# Power.net
KiCad netlist of a schematic drawn in EAGLE
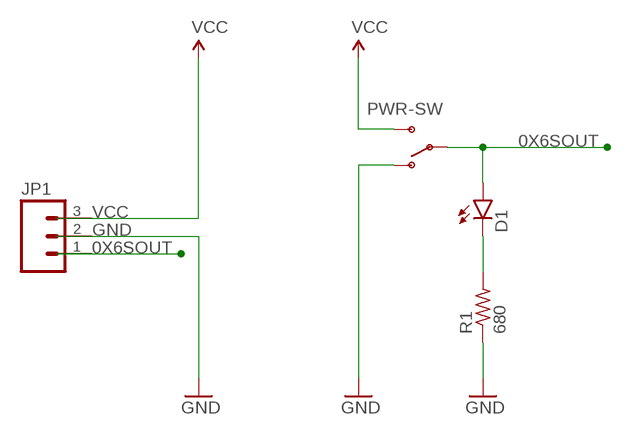
[diagram p0: schematic, sheet 1]

(export (version "E")
  (design (tool "Eeschema 10.0.6"))
  (components
    (comp (ref "D1")
      (value "LED3MM")
      (footprint "eagle-import:LED3MM")
      (libsource (lib "eagle-import") (part "LED3MM"))
    )
    (comp (ref "JP1")
      (value "M03PTH")
      (footprint "eagle-import:1X03")
      (libsource (lib "eagle-import") (part "M03PTH"))
    )
    (comp (ref "PWR-SW")
      (value "SWITCH-SPDTPTH")
      (footprint "eagle-import:SWITCH-SPDT")
      (libsource (lib "eagle-import") (part "SWITCH-SPDTPTH"))
    )
    (comp (ref "R1")
      (value "680")
      (footprint "eagle-import:R0603")
      (libsource (lib "eagle-import") (part "R-US_R0603"))
    )
  )
  (nets
    (net (code "1") (name "/0X6SOUT") (class "Default")
      (node (ref "D1") (pin "A") (pinfunction "A_A") (pintype "passive"))
      (node (ref "JP1") (pin "1") (pinfunction "1_1") (pintype "passive"))
      (node (ref "PWR-SW") (pin "2") (pinfunction "P_2") (pintype "passive"))
    )
    (net (code "2") (name "GND") (class "Default")
      (node (ref "JP1") (pin "2") (pinfunction "2_2") (pintype "passive"))
      (node (ref "PWR-SW") (pin "1") (pinfunction "O_1") (pintype "passive"))
      (node (ref "R1") (pin "1") (pinfunction "1_1") (pintype "passive"))
    )
    (net (code "3") (name "Net-(D1-C)") (class "Default")
      (node (ref "D1") (pin "K") (pinfunction "C_K") (pintype "passive"))
      (node (ref "R1") (pin "2") (pinfunction "2_2") (pintype "passive"))
    )
    (net (code "4") (name "VCC") (class "Default")
      (node (ref "JP1") (pin "3") (pinfunction "3_3") (pintype "passive"))
      (node (ref "PWR-SW") (pin "3") (pinfunction "S_3") (pintype "passive"))
    )
  )
)
